# PCB1.net
KiCad netlist of a schematic drawn in Altium Designer
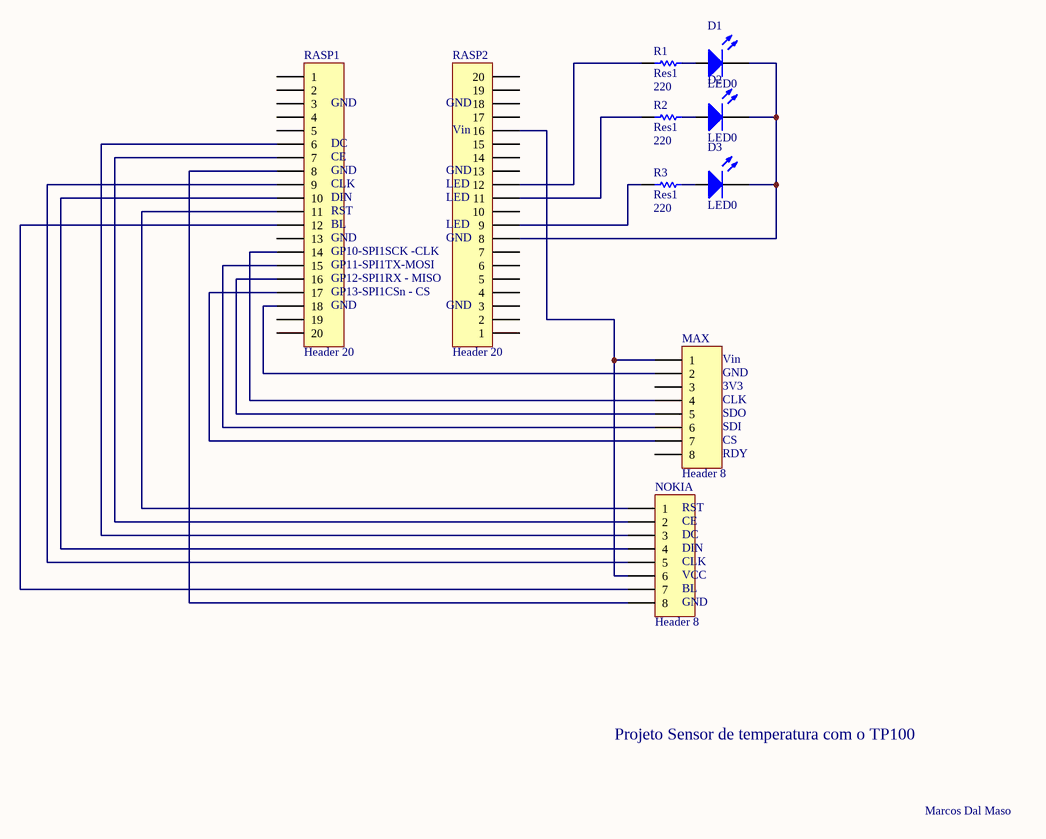
[diagram p0: PCB1.SchDoc]

(export (version "E")
  (design (tool "Eeschema 10.0.6"))
  (components
    (comp (ref "D1")
      (value "LED0")
      (footprint "LED-0")
      (description "Typical INFRARED GaAs LED")
      (fields (field (name "PUBLISHER") "Altium Limited"))
      (libsource (lib "Miscellaneous Devices") (part "LED0"))
    )
    (comp (ref "D2")
      (value "LED0")
      (footprint "LED-0")
      (description "Typical INFRARED GaAs LED")
      (fields (field (name "PUBLISHER") "Altium Limited"))
      (libsource (lib "Miscellaneous Devices") (part "LED0"))
    )
    (comp (ref "D3")
      (value "LED0")
      (footprint "LED-0")
      (description "Typical INFRARED GaAs LED")
      (fields (field (name "PUBLISHER") "Altium Limited"))
      (libsource (lib "Miscellaneous Devices") (part "LED0"))
    )
    (comp (ref "MAX")
      (value "Header 8")
      (footprint "HDR1X8")
      (description "Header, 8-Pin")
      (fields (field (name "PUBLISHER") "Altium Limited"))
      (libsource (lib "Miscellaneous Connectors") (part "Header 8"))
    )
    (comp (ref "NOKIA")
      (value "Header 8")
      (footprint "HDR1X8")
      (description "Header, 8-Pin")
      (fields (field (name "PUBLISHER") "Altium Limited"))
      (libsource (lib "Miscellaneous Connectors") (part "Header 8"))
    )
    (comp (ref "R1")
      (value "Res1")
      (footprint "AXIAL-0.3")
      (description "Resistor")
      (fields (field (name "ALTIUM_VALUE") "220") (field (name "PUBLISHER") "Altium Limited"))
      (libsource (lib "Miscellaneous Devices") (part "Res1"))
    )
    (comp (ref "R2")
      (value "Res1")
      (footprint "AXIAL-0.3")
      (description "Resistor")
      (fields (field (name "ALTIUM_VALUE") "220") (field (name "PUBLISHER") "Altium Limited"))
      (libsource (lib "Miscellaneous Devices") (part "Res1"))
    )
    (comp (ref "R3")
      (value "Res1")
      (footprint "AXIAL-0.3")
      (description "Resistor")
      (fields (field (name "ALTIUM_VALUE") "220") (field (name "PUBLISHER") "Altium Limited"))
      (libsource (lib "Miscellaneous Devices") (part "Res1"))
    )
    (comp (ref "RASP1")
      (value "Header 20")
      (footprint "HDR1X20")
      (description "Header, 20-Pin")
      (fields (field (name "PUBLISHER") "Altium Limited"))
      (libsource (lib "Miscellaneous Connectors") (part "Header 20"))
    )
    (comp (ref "RASP2")
      (value "Header 20")
      (footprint "HDR1X20")
      (description "Header, 20-Pin")
      (fields (field (name "PUBLISHER") "Altium Limited"))
      (libsource (lib "") (part "Header 20_1"))
    )
  )
  (nets
    (net (code "1") (name "Net-(D1-A)") (class "Default")
      (node (ref "D1") (pin "1") (pinfunction "A_1") (pintype "passive"))
      (node (ref "R1") (pin "2") (pinfunction "2_2") (pintype "passive"))
    )
    (net (code "2") (name "Net-(D1-K)") (class "Default")
      (node (ref "D1") (pin "2") (pinfunction "K_2") (pintype "passive"))
      (node (ref "D2") (pin "2") (pinfunction "K_2") (pintype "passive"))
      (node (ref "D3") (pin "2") (pinfunction "K_2") (pintype "passive"))
      (node (ref "RASP2") (pin "8") (pinfunction "8_8") (pintype "passive"))
    )
    (net (code "3") (name "Net-(D2-A)") (class "Default")
      (node (ref "D2") (pin "1") (pinfunction "A_1") (pintype "passive"))
      (node (ref "R2") (pin "2") (pinfunction "2_2") (pintype "passive"))
    )
    (net (code "4") (name "Net-(D3-A)") (class "Default")
      (node (ref "D3") (pin "1") (pinfunction "A_1") (pintype "passive"))
      (node (ref "R3") (pin "2") (pinfunction "2_2") (pintype "passive"))
    )
    (net (code "5") (name "Net-(MAX-Pad1)") (class "Default")
      (node (ref "MAX") (pin "1") (pinfunction "1_1") (pintype "passive"))
      (node (ref "NOKIA") (pin "6") (pinfunction "6_6") (pintype "passive"))
      (node (ref "RASP2") (pin "16") (pinfunction "16_16") (pintype "passive"))
    )
    (net (code "6") (name "Net-(MAX-Pad2)") (class "Default")
      (node (ref "MAX") (pin "2") (pinfunction "2_2") (pintype "passive"))
      (node (ref "RASP1") (pin "18") (pinfunction "18_18") (pintype "passive"))
    )
    (net (code "7") (name "Net-(MAX-Pad4)") (class "Default")
      (node (ref "MAX") (pin "4") (pinfunction "4_4") (pintype "passive"))
      (node (ref "RASP1") (pin "14") (pinfunction "14_14") (pintype "passive"))
    )
    (net (code "8") (name "Net-(MAX-Pad5)") (class "Default")
      (node (ref "MAX") (pin "5") (pinfunction "5_5") (pintype "passive"))
      (node (ref "RASP1") (pin "16") (pinfunction "16_16") (pintype "passive"))
    )
    (net (code "9") (name "Net-(MAX-Pad6)") (class "Default")
      (node (ref "MAX") (pin "6") (pinfunction "6_6") (pintype "passive"))
      (node (ref "RASP1") (pin "15") (pinfunction "15_15") (pintype "passive"))
    )
    (net (code "10") (name "Net-(MAX-Pad7)") (class "Default")
      (node (ref "MAX") (pin "7") (pinfunction "7_7") (pintype "passive"))
      (node (ref "RASP1") (pin "17") (pinfunction "17_17") (pintype "passive"))
    )
    (net (code "11") (name "Net-(NOKIA-Pad1)") (class "Default")
      (node (ref "NOKIA") (pin "1") (pinfunction "1_1") (pintype "passive"))
      (node (ref "RASP1") (pin "11") (pinfunction "11_11") (pintype "passive"))
    )
    (net (code "12") (name "Net-(NOKIA-Pad2)") (class "Default")
      (node (ref "NOKIA") (pin "2") (pinfunction "2_2") (pintype "passive"))
      (node (ref "RASP1") (pin "7") (pinfunction "7_7") (pintype "passive"))
    )
    (net (code "13") (name "Net-(NOKIA-Pad3)") (class "Default")
      (node (ref "NOKIA") (pin "3") (pinfunction "3_3") (pintype "passive"))
      (node (ref "RASP1") (pin "6") (pinfunction "6_6") (pintype "passive"))
    )
    (net (code "14") (name "Net-(NOKIA-Pad4)") (class "Default")
      (node (ref "NOKIA") (pin "4") (pinfunction "4_4") (pintype "passive"))
      (node (ref "RASP1") (pin "10") (pinfunction "10_10") (pintype "passive"))
    )
    (net (code "15") (name "Net-(NOKIA-Pad5)") (class "Default")
      (node (ref "NOKIA") (pin "5") (pinfunction "5_5") (pintype "passive"))
      (node (ref "RASP1") (pin "9") (pinfunction "9_9") (pintype "passive"))
    )
    (net (code "16") (name "Net-(NOKIA-Pad7)") (class "Default")
      (node (ref "NOKIA") (pin "7") (pinfunction "7_7") (pintype "passive"))
      (node (ref "RASP1") (pin "12") (pinfunction "12_12") (pintype "passive"))
    )
    (net (code "17") (name "Net-(NOKIA-Pad8)") (class "Default")
      (node (ref "NOKIA") (pin "8") (pinfunction "8_8") (pintype "passive"))
      (node (ref "RASP1") (pin "8") (pinfunction "8_8") (pintype "passive"))
    )
    (net (code "18") (name "Net-(R1-Pad1)") (class "Default")
      (node (ref "R1") (pin "1") (pinfunction "1_1") (pintype "passive"))
      (node (ref "RASP2") (pin "12") (pinfunction "12_12") (pintype "passive"))
    )
    (net (code "19") (name "Net-(R2-Pad1)") (class "Default")
      (node (ref "R2") (pin "1") (pinfunction "1_1") (pintype "passive"))
      (node (ref "RASP2") (pin "11") (pinfunction "11_11") (pintype "passive"))
    )
    (net (code "20") (name "Net-(R3-Pad1)") (class "Default")
      (node (ref "R3") (pin "1") (pinfunction "1_1") (pintype "passive"))
      (node (ref "RASP2") (pin "9") (pinfunction "9_9") (pintype "passive"))
    )
    (net (code "21") (name "unconnected-(MAX-Pad3)") (class "Default")
      (node (ref "MAX") (pin "3") (pinfunction "3_3") (pintype "passive"))
    )
    (net (code "22") (name "unconnected-(MAX-Pad8)") (class "Default")
      (node (ref "MAX") (pin "8") (pinfunction "8_8") (pintype "passive"))
    )
    (net (code "23") (name "unconnected-(RASP1-Pad1)") (class "Default")
      (node (ref "RASP1") (pin "1") (pinfunction "1_1") (pintype "passive"))
    )
    (net (code "24") (name "unconnected-(RASP1-Pad2)") (class "Default")
      (node (ref "RASP1") (pin "2") (pinfunction "2_2") (pintype "passive"))
    )
    (net (code "25") (name "unconnected-(RASP1-Pad3)") (class "Default")
      (node (ref "RASP1") (pin "3") (pinfunction "3_3") (pintype "passive"))
    )
    (net (code "26") (name "unconnected-(RASP1-Pad4)") (class "Default")
      (node (ref "RASP1") (pin "4") (pinfunction "4_4") (pintype "passive"))
    )
    (net (code "27") (name "unconnected-(RASP1-Pad5)") (class "Default")
      (node (ref "RASP1") (pin "5") (pinfunction "5_5") (pintype "passive"))
    )
    (net (code "28") (name "unconnected-(RASP1-Pad13)") (class "Default")
      (node (ref "RASP1") (pin "13") (pinfunction "13_13") (pintype "passive"))
    )
    (net (code "29") (name "unconnected-(RASP1-Pad19)") (class "Default")
      (node (ref "RASP1") (pin "19") (pinfunction "19_19") (pintype "passive"))
    )
    (net (code "30") (name "unconnected-(RASP1-Pad20)") (class "Default")
      (node (ref "RASP1") (pin "20") (pinfunction "20_20") (pintype "passive"))
    )
    (net (code "31") (name "unconnected-(RASP2-Pad1)") (class "Default")
      (node (ref "RASP2") (pin "1") (pinfunction "1_1") (pintype "passive"))
    )
    (net (code "32") (name "unconnected-(RASP2-Pad2)") (class "Default")
      (node (ref "RASP2") (pin "2") (pinfunction "2_2") (pintype "passive"))
    )
    (net (code "33") (name "unconnected-(RASP2-Pad3)") (class "Default")
      (node (ref "RASP2") (pin "3") (pinfunction "3_3") (pintype "passive"))
    )
    (net (code "34") (name "unconnected-(RASP2-Pad4)") (class "Default")
      (node (ref "RASP2") (pin "4") (pinfunction "4_4") (pintype "passive"))
    )
    (net (code "35") (name "unconnected-(RASP2-Pad5)") (class "Default")
      (node (ref "RASP2") (pin "5") (pinfunction "5_5") (pintype "passive"))
    )
    (net (code "36") (name "unconnected-(RASP2-Pad6)") (class "Default")
      (node (ref "RASP2") (pin "6") (pinfunction "6_6") (pintype "passive"))
    )
    (net (code "37") (name "unconnected-(RASP2-Pad7)") (class "Default")
      (node (ref "RASP2") (pin "7") (pinfunction "7_7") (pintype "passive"))
    )
    (net (code "38") (name "unconnected-(RASP2-Pad10)") (class "Default")
      (node (ref "RASP2") (pin "10") (pinfunction "10_10") (pintype "passive"))
    )
    (net (code "39") (name "unconnected-(RASP2-Pad13)") (class "Default")
      (node (ref "RASP2") (pin "13") (pinfunction "13_13") (pintype "passive"))
    )
    (net (code "40") (name "unconnected-(RASP2-Pad14)") (class "Default")
      (node (ref "RASP2") (pin "14") (pinfunction "14_14") (pintype "passive"))
    )
    (net (code "41") (name "unconnected-(RASP2-Pad15)") (class "Default")
      (node (ref "RASP2") (pin "15") (pinfunction "15_15") (pintype "passive"))
    )
    (net (code "42") (name "unconnected-(RASP2-Pad17)") (class "Default")
      (node (ref "RASP2") (pin "17") (pinfunction "17_17") (pintype "passive"))
    )
    (net (code "43") (name "unconnected-(RASP2-Pad18)") (class "Default")
      (node (ref "RASP2") (pin "18") (pinfunction "18_18") (pintype "passive"))
    )
    (net (code "44") (name "unconnected-(RASP2-Pad19)") (class "Default")
      (node (ref "RASP2") (pin "19") (pinfunction "19_19") (pintype "passive"))
    )
    (net (code "45") (name "unconnected-(RASP2-Pad20)") (class "Default")
      (node (ref "RASP2") (pin "20") (pinfunction "20_20") (pintype "passive"))
    )
  )
)
